# compactModalAccel.net
KiCad netlist of a schematic drawn in Altium Designer
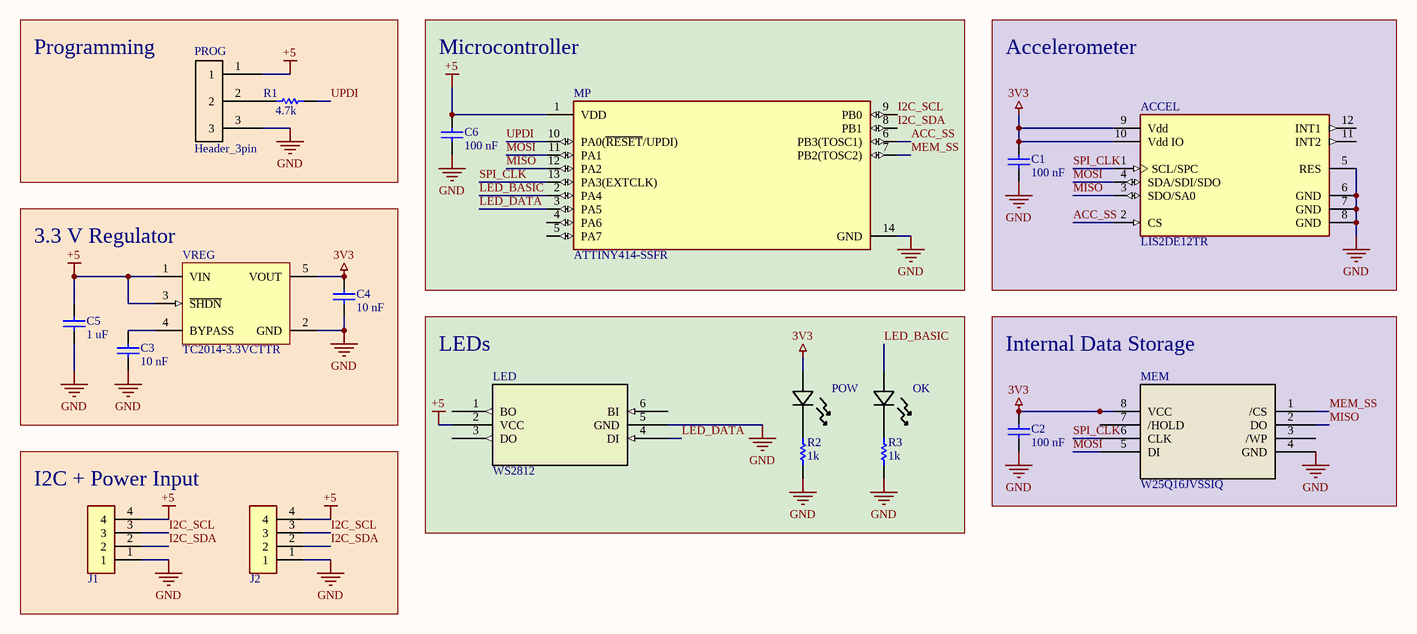
[diagram p0: compactModalAccel.SchDoc]

(export (version "E")
  (design (tool "Eeschema 10.0.6"))
  (components
    (comp (ref "ACCEL")
      (value "LIS2DE12TR")
      (footprint "FP-LGA-12-8365767-MFG")
      (description "ACCEL 2-16G I2C/SPI 12LGA")
      (libsource (lib "Altium Content Vault") (part "23187633e68d3cc9467fe28228126c6"))
    )
    (comp (ref "C1")
      (value "100 nF")
      (footprint "CAPC1608X95X40ML15T15")
      (fields (field (name "MANUFACTURER") "Vitramon") (field (name "PART NUMBER") "VJ0603Y104KXQCW1BC"))
      (libsource (lib "Altium Content Vault") (part "CAP"))
    )
    (comp (ref "C2")
      (value "100 nF")
      (footprint "CAPC1608X95X40ML15T15")
      (fields (field (name "MANUFACTURER") "Vitramon") (field (name "PART NUMBER") "VJ0603Y104KXQCW1BC"))
      (libsource (lib "Altium Content Vault") (part "CAP"))
    )
    (comp (ref "C3")
      (value "10 nF")
      (footprint "CAPC1608X95X40ML15T15")
      (fields (field (name "MANUFACTURER") "Vitramon") (field (name "PART NUMBER") "VJ0603Y104KXQCW1BC"))
      (libsource (lib "Altium Content Vault") (part "CAP"))
    )
    (comp (ref "C4")
      (value "10 nF")
      (footprint "CAPC1608X95X40ML15T15")
      (fields (field (name "MANUFACTURER") "Vitramon") (field (name "PART NUMBER") "VJ0603Y104KXQCW1BC"))
      (libsource (lib "Altium Content Vault") (part "CAP"))
    )
    (comp (ref "C5")
      (value "1 uF")
      (footprint "CAPC1608X95X40ML15T15")
      (fields (field (name "MANUFACTURER") "Vitramon") (field (name "PART NUMBER") "VJ0603Y104KXQCW1BC"))
      (libsource (lib "Altium Content Vault") (part "CAP"))
    )
    (comp (ref "C6")
      (value "100 nF")
      (footprint "CAPC1608X95X40ML15T15")
      (fields (field (name "MANUFACTURER") "Vitramon") (field (name "PART NUMBER") "VJ0603Y104KXQCW1BC"))
      (libsource (lib "Altium Content Vault") (part "CAP"))
    )
    (comp (ref "J1")
      (value "B4B-XH-A(LF)(SN)")
      (footprint "JST_B4B-XH-A(LF)(SN)")
      (description "Connector Header Through Hole 4 position 0.098 (2.50mm)")
      (fields (field (name "MF") "JST Sales") (field (name "SOURCE") "MainEnclosure.SchLib"))
      (libsource (lib "Yonder Dynamics - 2022-2023") (part "B4B-XH-A(LF)(SN)"))
    )
    (comp (ref "J2")
      (value "B4B-XH-A(LF)(SN)")
      (footprint "JST_B4B-XH-A(LF)(SN)")
      (description "Connector Header Through Hole 4 position 0.098 (2.50mm)")
      (fields (field (name "MF") "JST Sales") (field (name "SOURCE") "MainEnclosure.SchLib"))
      (libsource (lib "Yonder Dynamics - 2022-2023") (part "B4B-XH-A(LF)(SN)"))
    )
    (comp (ref "LED")
      (value "WS2812")
      (footprint "WS2812_WDS")
      (description "Addressable LED")
      (fields (field (name "COPYRIGHT") "Copyright (C) 2023 Ultra Librarian. All rights reserved."))
      (libsource (lib "Yonder Dynamics - 2022-2023") (part "WS2812"))
    )
    (comp (ref "MEM")
      (value "W25Q16JVSSIQ")
      (footprint "W25Q16JVSSIQ_WIN")
      (description "No Description Available")
      (fields (field (name "COPYRIGHT") "Copyright (C) 2023 Ultra Librarian. All rights reserved."))
      (libsource (lib "Yonder Dynamics - 2022-2023") (part "W25Q16JVSSIQ"))
    )
    (comp (ref "MP")
      (value "ATTINY414-SSFR")
      (footprint "FP-C04-065-SL-IPC_A")
      (description "IC MCU 8BIT 4KB FLASH 14SOIC")
      (libsource (lib "Altium Content Vault") (part "b60545129d1f4d357a4b73cc7cce6dc"))
    )
    (comp (ref "OK")
      (value "HSMH-C170")
      (footprint "LED_HSMx-C170_AVA")
      (description "No Description Available")
      (fields (field (name "COPYRIGHT") "Copyright (C) 2023 Ultra Librarian. All rights reserved."))
      (libsource (lib "Yonder Dynamics - 2022-2023") (part "HSMH-C170"))
    )
    (comp (ref "POW")
      (value "HSMH-C170")
      (footprint "LED_HSMx-C170_AVA")
      (description "No Description Available")
      (fields (field (name "COPYRIGHT") "Copyright (C) 2023 Ultra Librarian. All rights reserved."))
      (libsource (lib "Yonder Dynamics - 2022-2023") (part "HSMH-C170"))
    )
    (comp (ref "PROG")
      (value "Header_3pin")
      (footprint "3pinHeader")
      (fields (field (name "SOURCE") "MainEnclosure.SchLib"))
      (libsource (lib "Yonder Dynamics - 2022-2023") (part "Header_3pin"))
    )
    (comp (ref "R1")
      (value "4.7k")
      (footprint "RESC1609X50X30NL10T20")
      (fields (field (name "MANUFACTURER") "Vishay Dale") (field (name "PART NUMBER") "CRCW06034K70FKTA"))
      (libsource (lib "Altium Content Vault") (part "RES"))
    )
    (comp (ref "R2")
      (value "1k")
      (footprint "RESC1609X50X30NL10T20")
      (fields (field (name "MANUFACTURER") "Vishay Dale") (field (name "PART NUMBER") "CRCW06034K70FKTA"))
      (libsource (lib "Altium Content Vault") (part "RES"))
    )
    (comp (ref "R3")
      (value "1k")
      (footprint "RESC1609X50X30NL10T20")
      (fields (field (name "MANUFACTURER") "Vishay Dale") (field (name "PART NUMBER") "CRCW06034K70FKTA"))
      (libsource (lib "Altium Content Vault") (part "RES"))
    )
    (comp (ref "VREG")
      (value "TC2014-3.3VCTTR")
      (footprint "SOT-23-CT5_M")
      (libsource (lib "Altium Content Vault") (part "PM-LINEREG-TC2014-IL5"))
    )
  )
  (nets
    (net (code "1") (name "+5") (class "Default")
      (node (ref "C5") (pin "1") (pinfunction "1_1") (pintype "passive"))
      (node (ref "C6") (pin "1") (pinfunction "1_1") (pintype "passive"))
      (node (ref "J1") (pin "4") (pinfunction "4_4") (pintype "passive"))
      (node (ref "J2") (pin "4") (pinfunction "4_4") (pintype "passive"))
      (node (ref "LED") (pin "2") (pinfunction "VCC_2") (pintype "power_in"))
      (node (ref "MP") (pin "1") (pinfunction "VDD_1") (pintype "power_in"))
      (node (ref "PROG") (pin "1") (pinfunction "1_1") (pintype "passive"))
      (node (ref "VREG") (pin "1") (pinfunction "VIN_1") (pintype "power_in"))
      (node (ref "VREG") (pin "3") (pinfunction "~{SHDN}_3") (pintype "input"))
    )
    (net (code "2") (name "/ACC_SS") (class "Default")
      (node (ref "ACCEL") (pin "2") (pinfunction "CS_2") (pintype "input"))
      (node (ref "MP") (pin "6") (pinfunction "PB3(TOSC1)_6") (pintype "bidirectional"))
    )
    (net (code "3") (name "/I2C_SCL") (class "Default")
      (node (ref "J1") (pin "3") (pinfunction "3_3") (pintype "passive"))
      (node (ref "J2") (pin "3") (pinfunction "3_3") (pintype "passive"))
      (node (ref "MP") (pin "9") (pinfunction "PB0_9") (pintype "bidirectional"))
    )
    (net (code "4") (name "/I2C_SDA") (class "Default")
      (node (ref "J1") (pin "2") (pinfunction "2_2") (pintype "passive"))
      (node (ref "J2") (pin "2") (pinfunction "2_2") (pintype "passive"))
      (node (ref "MP") (pin "8") (pinfunction "PB1_8") (pintype "bidirectional"))
    )
    (net (code "5") (name "/LED_BASIC") (class "Default")
      (node (ref "MP") (pin "2") (pinfunction "PA4_2") (pintype "bidirectional"))
      (node (ref "OK") (pin "2") (pinfunction "2_2") (pintype "passive"))
    )
    (net (code "6") (name "/LED_DATA") (class "Default")
      (node (ref "LED") (pin "4") (pinfunction "DI_4") (pintype "input"))
      (node (ref "MP") (pin "3") (pinfunction "PA5_3") (pintype "bidirectional"))
    )
    (net (code "7") (name "/MEM_SS") (class "Default")
      (node (ref "MEM") (pin "1") (pinfunction "/CS_1") (pintype "passive"))
      (node (ref "MP") (pin "7") (pinfunction "PB2(TOSC2)_7") (pintype "bidirectional"))
    )
    (net (code "8") (name "/MISO") (class "Default")
      (node (ref "ACCEL") (pin "3") (pinfunction "SDO/SA0_3") (pintype "bidirectional"))
      (node (ref "MEM") (pin "2") (pinfunction "DO_2") (pintype "passive"))
      (node (ref "MP") (pin "12") (pinfunction "PA2_12") (pintype "bidirectional"))
    )
    (net (code "9") (name "/MOSI") (class "Default")
      (node (ref "ACCEL") (pin "4") (pinfunction "SDA/SDI/SDO_4") (pintype "bidirectional"))
      (node (ref "MEM") (pin "5") (pinfunction "DI_5") (pintype "passive"))
      (node (ref "MP") (pin "11") (pinfunction "PA1_11") (pintype "bidirectional"))
    )
    (net (code "10") (name "/SPI_CLK") (class "Default")
      (node (ref "ACCEL") (pin "1") (pinfunction "SCL/SPC_1") (pintype "input"))
      (node (ref "MEM") (pin "6") (pinfunction "CLK_6") (pintype "passive"))
      (node (ref "MP") (pin "13") (pinfunction "PA3(EXTCLK)_13") (pintype "bidirectional"))
    )
    (net (code "11") (name "/UPDI") (class "Default")
      (node (ref "MP") (pin "10") (pinfunction "PA0(~{RESET}/UPDI)_10") (pintype "bidirectional"))
      (node (ref "R1") (pin "2") (pinfunction "2_2") (pintype "passive"))
    )
    (net (code "12") (name "3V3") (class "Default")
      (node (ref "ACCEL") (pin "10") (pinfunction "Vdd_IO_10") (pintype "power_in"))
      (node (ref "ACCEL") (pin "9") (pinfunction "Vdd_9") (pintype "power_in"))
      (node (ref "C1") (pin "1") (pinfunction "1_1") (pintype "passive"))
      (node (ref "C2") (pin "1") (pinfunction "1_1") (pintype "passive"))
      (node (ref "C4") (pin "1") (pinfunction "1_1") (pintype "passive"))
      (node (ref "MEM") (pin "8") (pinfunction "VCC_8") (pintype "passive"))
      (node (ref "POW") (pin "2") (pinfunction "2_2") (pintype "passive"))
      (node (ref "VREG") (pin "5") (pinfunction "VOUT_5") (pintype "power_in"))
    )
    (net (code "13") (name "GND") (class "Default")
      (node (ref "ACCEL") (pin "5") (pinfunction "RES_5") (pintype "passive"))
      (node (ref "ACCEL") (pin "6") (pinfunction "GND_6") (pintype "power_in"))
      (node (ref "ACCEL") (pin "7") (pinfunction "GND_7") (pintype "power_in"))
      (node (ref "ACCEL") (pin "8") (pinfunction "GND_8") (pintype "power_in"))
      (node (ref "C1") (pin "2") (pinfunction "2_2") (pintype "passive"))
      (node (ref "C2") (pin "2") (pinfunction "2_2") (pintype "passive"))
      (node (ref "C3") (pin "2") (pinfunction "2_2") (pintype "passive"))
      (node (ref "C4") (pin "2") (pinfunction "2_2") (pintype "passive"))
      (node (ref "C5") (pin "2") (pinfunction "2_2") (pintype "passive"))
      (node (ref "C6") (pin "2") (pinfunction "2_2") (pintype "passive"))
      (node (ref "J1") (pin "1") (pinfunction "1_1") (pintype "passive"))
      (node (ref "J2") (pin "1") (pinfunction "1_1") (pintype "passive"))
      (node (ref "LED") (pin "5") (pinfunction "GND_5") (pintype "power_in"))
      (node (ref "MEM") (pin "4") (pinfunction "GND_4") (pintype "passive"))
      (node (ref "MP") (pin "14") (pinfunction "GND_14") (pintype "power_in"))
      (node (ref "PROG") (pin "3") (pinfunction "3_3") (pintype "passive"))
      (node (ref "R2") (pin "2") (pinfunction "2_2") (pintype "passive"))
      (node (ref "R3") (pin "2") (pinfunction "2_2") (pintype "passive"))
      (node (ref "VREG") (pin "2") (pinfunction "GND_2") (pintype "power_in"))
    )
    (net (code "14") (name "Net-(OK-Pad1)") (class "Default")
      (node (ref "OK") (pin "1") (pinfunction "1_1") (pintype "passive"))
      (node (ref "R3") (pin "1") (pinfunction "1_1") (pintype "passive"))
    )
    (net (code "15") (name "Net-(POW-Pad1)") (class "Default")
      (node (ref "POW") (pin "1") (pinfunction "1_1") (pintype "passive"))
      (node (ref "R2") (pin "1") (pinfunction "1_1") (pintype "passive"))
    )
    (net (code "16") (name "Net-(PROG-Pad2)") (class "Default")
      (node (ref "PROG") (pin "2") (pinfunction "2_2") (pintype "passive"))
      (node (ref "R1") (pin "1") (pinfunction "1_1") (pintype "passive"))
    )
    (net (code "17") (name "Net-(VREG-BYPASS)") (class "Default")
      (node (ref "C3") (pin "1") (pinfunction "1_1") (pintype "passive"))
      (node (ref "VREG") (pin "4") (pinfunction "BYPASS_4") (pintype "passive"))
    )
    (net (code "18") (name "unconnected-(ACCEL-INT1-Pad12)") (class "Default")
      (node (ref "ACCEL") (pin "12") (pinfunction "INT1_12") (pintype "output"))
    )
    (net (code "19") (name "unconnected-(ACCEL-INT2-Pad11)") (class "Default")
      (node (ref "ACCEL") (pin "11") (pinfunction "INT2_11") (pintype "output"))
    )
    (net (code "20") (name "unconnected-(LED-BI-Pad6)") (class "Default")
      (node (ref "LED") (pin "6") (pinfunction "BI_6") (pintype "input"))
    )
    (net (code "21") (name "unconnected-(LED-BO-Pad1)") (class "Default")
      (node (ref "LED") (pin "1") (pinfunction "BO_1") (pintype "output"))
    )
    (net (code "22") (name "unconnected-(LED-DO-Pad3)") (class "Default")
      (node (ref "LED") (pin "3") (pinfunction "DO_3") (pintype "output"))
    )
    (net (code "23") (name "unconnected-(MEM-{slash}HOLD-Pad7)") (class "Default")
      (node (ref "MEM") (pin "7") (pinfunction "/HOLD_7") (pintype "passive"))
    )
    (net (code "24") (name "unconnected-(MEM-{slash}WP-Pad3)") (class "Default")
      (node (ref "MEM") (pin "3") (pinfunction "/WP_3") (pintype "passive"))
    )
    (net (code "25") (name "unconnected-(MP-PA6-Pad4)") (class "Default")
      (node (ref "MP") (pin "4") (pinfunction "PA6_4") (pintype "bidirectional"))
    )
    (net (code "26") (name "unconnected-(MP-PA7-Pad5)") (class "Default")
      (node (ref "MP") (pin "5") (pinfunction "PA7_5") (pintype "bidirectional"))
    )
  )
)
